# MAIN_DRIVER.net
KiCad netlist of a schematic drawn in Altium Designer
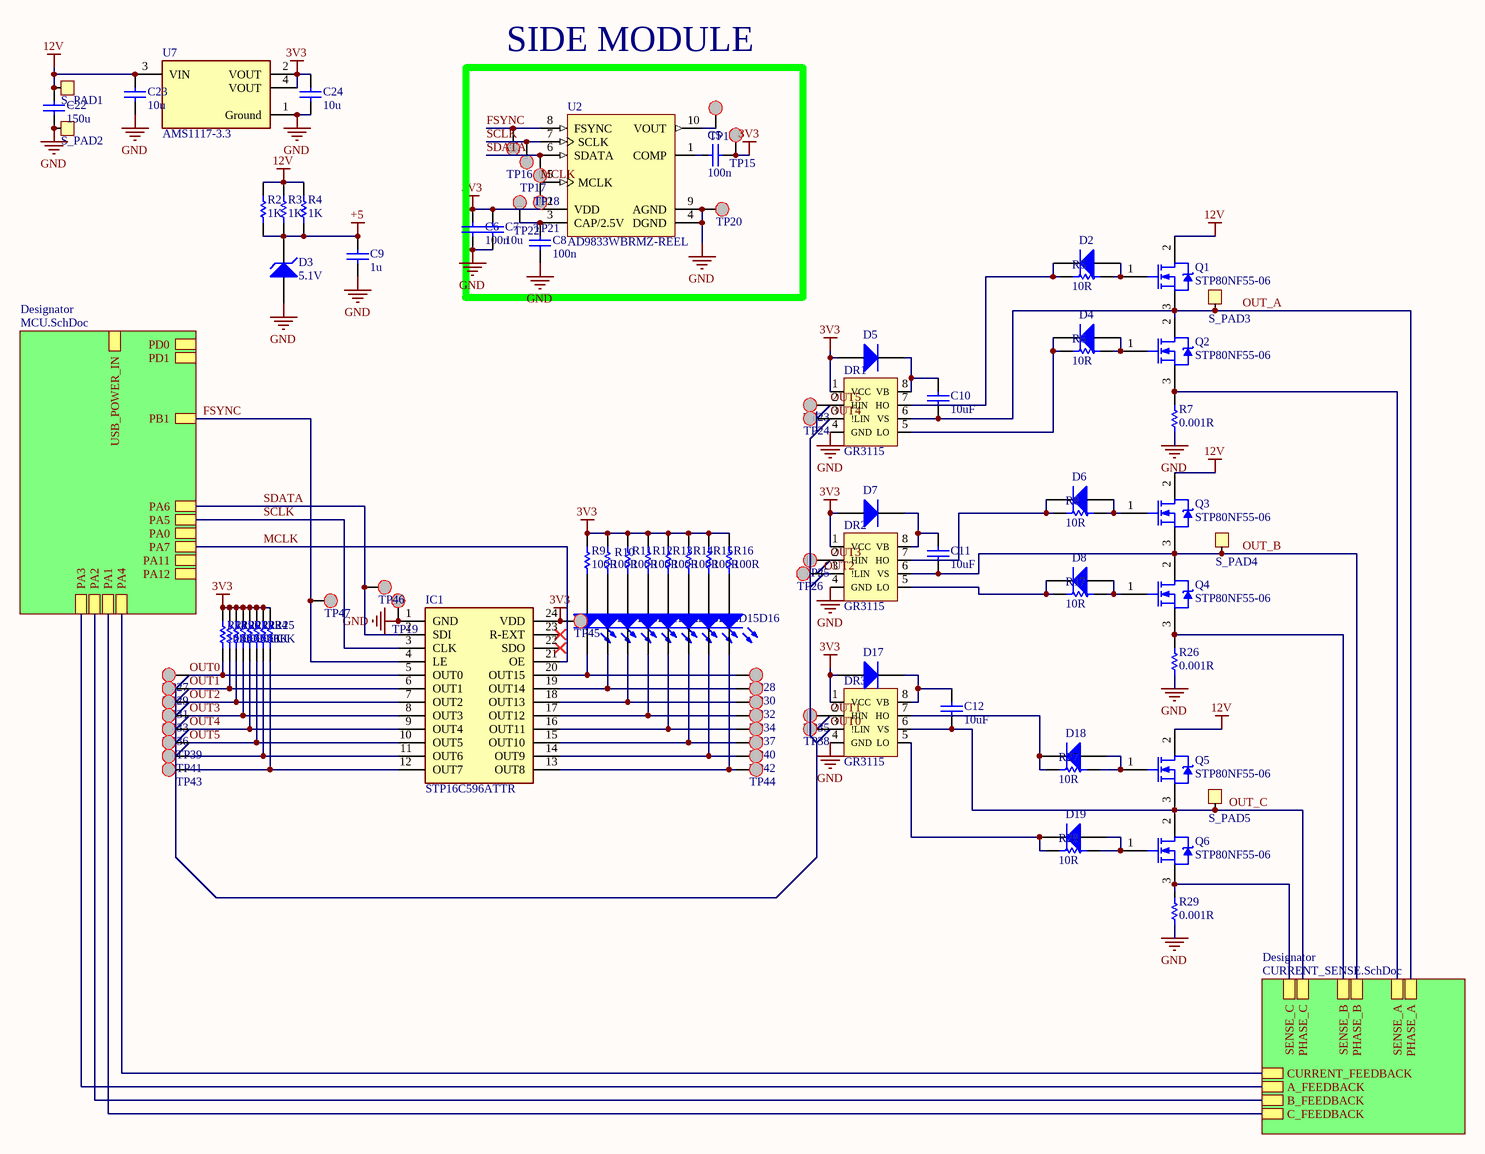
[diagram p0: MAIN_DRIVER.SchDoc]

(export (version "E")
  (design (tool "Eeschema 10.0.6"))
  (components
    (comp (ref "C5")
      (value "100n")
      (footprint "CAP FILM 0603_1608")
      (description "Capacitor")
      (libsource (lib "Simulation Generic Components") (part "Capacitor"))
    )
    (comp (ref "C6")
      (value "100n")
      (footprint "CAP FILM 0603_1608")
      (description "Capacitor")
      (libsource (lib "Simulation Generic Components") (part "Capacitor"))
    )
    (comp (ref "C7")
      (value "10u")
      (footprint "CAP FILM 0603_1608")
      (description "Capacitor")
      (libsource (lib "Simulation Generic Components") (part "Capacitor"))
    )
    (comp (ref "C8")
      (value "100n")
      (footprint "CAP FILM 0603_1608")
      (description "Capacitor")
      (libsource (lib "Simulation Generic Components") (part "Capacitor"))
    )
    (comp (ref "C9")
      (value "1u")
      (footprint "CAP FILM 0603_1608")
      (description "Capacitor")
      (libsource (lib "Simulation Generic Components") (part "Capacitor"))
    )
    (comp (ref "C10")
      (value "10uF")
      (footprint "CAP FILM 0603_1608")
      (description "Capacitor")
      (libsource (lib "Simulation Generic Components") (part "Capacitor"))
    )
    (comp (ref "C11")
      (value "10uF")
      (footprint "CAP FILM 0603_1608")
      (description "Capacitor")
      (libsource (lib "Simulation Generic Components") (part "Capacitor"))
    )
    (comp (ref "C12")
      (value "10uF")
      (footprint "CAP FILM 0603_1608")
      (description "Capacitor")
      (libsource (lib "Simulation Generic Components") (part "Capacitor"))
    )
    (comp (ref "C22")
      (value "150u")
      (footprint "CAPAE7266X80M")
      (description "Capacitor")
      (libsource (lib "Simulation Generic Components") (part "Capacitor"))
    )
    (comp (ref "C23")
      (value "10u")
      (footprint "CAP FILM 0805")
      (description "Capacitor")
      (libsource (lib "Simulation Generic Components") (part "Capacitor"))
    )
    (comp (ref "C24")
      (value "10u")
      (footprint "CAP FILM 0805")
      (description "Capacitor")
      (libsource (lib "Simulation Generic Components") (part "Capacitor"))
    )
    (comp (ref "D2")
      (value "1N4148")
      (footprint "SODFL375X135-2N")
      (description "Diode")
      (libsource (lib "Simulation Generic Components") (part "Diode"))
    )
    (comp (ref "D3")
      (value "Zener Diode")
      (footprint "DIOMELF3514N")
      (fields (field (name "BV") "5.1V"))
      (libsource (lib "Simulation Generic Components") (part "Zener Diode"))
    )
    (comp (ref "D4")
      (value "1N4148")
      (footprint "SODFL375X135-2N")
      (description "Diode")
      (libsource (lib "Simulation Generic Components") (part "Diode"))
    )
    (comp (ref "D5")
      (value "Diode")
      (footprint "SODFL365X110-2N")
      (libsource (lib "Simulation Generic Components") (part "Diode"))
    )
    (comp (ref "D6")
      (value "1N4148")
      (footprint "SODFL375X135-2N")
      (description "Diode")
      (libsource (lib "Simulation Generic Components") (part "Diode"))
    )
    (comp (ref "D7")
      (value "Diode")
      (footprint "SODFL365X110-2N")
      (libsource (lib "Simulation Generic Components") (part "Diode"))
    )
    (comp (ref "D8")
      (value "1N4148")
      (footprint "SODFL375X135-2N")
      (description "Diode")
      (libsource (lib "Simulation Generic Components") (part "Diode"))
    )
    (comp (ref "D9")
      (value "Light-Emitting Diode")
      (footprint "RES 0603_1608")
      (libsource (lib "Simulation Generic Components") (part "LED"))
    )
    (comp (ref "D10")
      (value "Light-Emitting Diode")
      (footprint "RES 0603_1608")
      (libsource (lib "Simulation Generic Components") (part "LED"))
    )
    (comp (ref "D11")
      (value "Light-Emitting Diode")
      (footprint "RES 0603_1608")
      (libsource (lib "Simulation Generic Components") (part "LED"))
    )
    (comp (ref "D12")
      (value "Light-Emitting Diode")
      (footprint "RES 0603_1608")
      (libsource (lib "Simulation Generic Components") (part "LED"))
    )
    (comp (ref "D13")
      (value "Light-Emitting Diode")
      (footprint "RES 0603_1608")
      (libsource (lib "Simulation Generic Components") (part "LED"))
    )
    (comp (ref "D14")
      (value "Light-Emitting Diode")
      (footprint "RES 0603_1608")
      (libsource (lib "Simulation Generic Components") (part "LED"))
    )
    (comp (ref "D15")
      (value "Light-Emitting Diode")
      (footprint "RES 0603_1608")
      (libsource (lib "Simulation Generic Components") (part "LED"))
    )
    (comp (ref "D16")
      (value "Light-Emitting Diode")
      (footprint "RES 0603_1608")
      (libsource (lib "Simulation Generic Components") (part "LED"))
    )
    (comp (ref "D17")
      (value "Diode")
      (footprint "SODFL365X110-2N")
      (libsource (lib "Simulation Generic Components") (part "Diode"))
    )
    (comp (ref "D18")
      (value "1N4148")
      (footprint "SODFL375X135-2N")
      (description "Diode")
      (libsource (lib "Simulation Generic Components") (part "Diode"))
    )
    (comp (ref "D19")
      (value "1N4148")
      (footprint "SODFL375X135-2N")
      (description "Diode")
      (libsource (lib "Simulation Generic Components") (part "Diode"))
    )
    (comp (ref "DR1")
      (value "GR3115")
      (footprint "PCBComponent_1")
      (libsource (lib "GR3115") (part "GR3115"))
    )
    (comp (ref "DR2")
      (value "GR3115")
      (footprint "PCBComponent_1")
      (libsource (lib "GR3115") (part "GR3115"))
    )
    (comp (ref "DR3")
      (value "GR3115")
      (footprint "PCBComponent_1")
      (libsource (lib "GR3115") (part "GR3115"))
    )
    (comp (ref "IC1")
      (value "STP16C596ATTR")
      (footprint "SamacSys:SOP65P638X110-24N")
      (description "Integrated Circuit")
      (libsource (lib "*") (part "STP16C596ATTR"))
    )
    (comp (ref "Q1")
      (value "STP80NF55-06")
      (footprint "STM-TO-220A-3")
      (fields (field (name "MANUFACTURER") "STMicroelectronics"))
      (libsource (lib "Altium Content Vault") (part "NEMOS-GDS-3_B"))
    )
    (comp (ref "Q2")
      (value "STP80NF55-06")
      (footprint "STM-TO-220A-3")
      (fields (field (name "MANUFACTURER") "STMicroelectronics"))
      (libsource (lib "Altium Content Vault") (part "NEMOS-GDS-3_B"))
    )
    (comp (ref "Q3")
      (value "STP80NF55-06")
      (footprint "STM-TO-220A-3")
      (fields (field (name "MANUFACTURER") "STMicroelectronics"))
      (libsource (lib "Altium Content Vault") (part "NEMOS-GDS-3_B"))
    )
    (comp (ref "Q4")
      (value "STP80NF55-06")
      (footprint "STM-TO-220A-3")
      (fields (field (name "MANUFACTURER") "STMicroelectronics"))
      (libsource (lib "Altium Content Vault") (part "NEMOS-GDS-3_B"))
    )
    (comp (ref "Q5")
      (value "STP80NF55-06")
      (footprint "STM-TO-220A-3")
      (fields (field (name "MANUFACTURER") "STMicroelectronics"))
      (libsource (lib "Altium Content Vault") (part "NEMOS-GDS-3_B"))
    )
    (comp (ref "Q6")
      (value "STP80NF55-06")
      (footprint "STM-TO-220A-3")
      (fields (field (name "MANUFACTURER") "STMicroelectronics"))
      (libsource (lib "Altium Content Vault") (part "NEMOS-GDS-3_B"))
    )
    (comp (ref "R2")
      (value "1K")
      (footprint "RES 0603_1608")
      (description "Resistor")
      (libsource (lib "Simulation Generic Components") (part "Resistor"))
    )
    (comp (ref "R3")
      (value "1K")
      (footprint "RES 0603_1608")
      (description "Resistor")
      (libsource (lib "Simulation Generic Components") (part "Resistor"))
    )
    (comp (ref "R4")
      (value "1K")
      (footprint "RES 0603_1608")
      (description "Resistor")
      (libsource (lib "Simulation Generic Components") (part "Resistor"))
    )
    (comp (ref "R5")
      (value "10R")
      (footprint "RES 0603_1608")
      (description "Resistor")
      (libsource (lib "Simulation Generic Components") (part "Resistor"))
    )
    (comp (ref "R6")
      (value "10R")
      (footprint "RES 0603_1608")
      (description "Resistor")
      (libsource (lib "Simulation Generic Components") (part "Resistor"))
    )
    (comp (ref "R7")
      (value "0.001R")
      (footprint "RES 1206_3216")
      (description "Resistor")
      (libsource (lib "Simulation Generic Components") (part "Resistor"))
    )
    (comp (ref "R8")
      (value "10R")
      (footprint "RES 0603_1608")
      (description "Resistor")
      (libsource (lib "Simulation Generic Components") (part "Resistor"))
    )
    (comp (ref "R9")
      (value "100R")
      (footprint "RES 0603_1608")
      (description "Resistor")
      (libsource (lib "Simulation Generic Components") (part "Resistor"))
    )
    (comp (ref "R10")
      (value "100R")
      (footprint "RES 0603_1608")
      (description "Resistor")
      (libsource (lib "Simulation Generic Components") (part "Resistor"))
    )
    (comp (ref "R11")
      (value "100R")
      (footprint "RES 0603_1608")
      (description "Resistor")
      (libsource (lib "Simulation Generic Components") (part "Resistor"))
    )
    (comp (ref "R12")
      (value "100R")
      (footprint "RES 0603_1608")
      (description "Resistor")
      (libsource (lib "Simulation Generic Components") (part "Resistor"))
    )
    (comp (ref "R13")
      (value "100R")
      (footprint "RES 0603_1608")
      (description "Resistor")
      (libsource (lib "Simulation Generic Components") (part "Resistor"))
    )
    (comp (ref "R14")
      (value "100R")
      (footprint "RES 0603_1608")
      (description "Resistor")
      (libsource (lib "Simulation Generic Components") (part "Resistor"))
    )
    (comp (ref "R15")
      (value "100R")
      (footprint "RES 0603_1608")
      (description "Resistor")
      (libsource (lib "Simulation Generic Components") (part "Resistor"))
    )
    (comp (ref "R16")
      (value "100R")
      (footprint "RES 0603_1608")
      (description "Resistor")
      (libsource (lib "Simulation Generic Components") (part "Resistor"))
    )
    (comp (ref "R17")
      (value "10R")
      (footprint "RES 0603_1608")
      (description "Resistor")
      (libsource (lib "Simulation Generic Components") (part "Resistor"))
    )
    (comp (ref "R18")
      (value "10K")
      (footprint "RES 0603_1608")
      (description "Resistor")
      (libsource (lib "Simulation Generic Components") (part "Resistor"))
    )
    (comp (ref "R19")
      (value "10K")
      (footprint "RES 0603_1608")
      (description "Resistor")
      (libsource (lib "Simulation Generic Components") (part "Resistor"))
    )
    (comp (ref "R20")
      (value "10K")
      (footprint "RES 0603_1608")
      (description "Resistor")
      (libsource (lib "Simulation Generic Components") (part "Resistor"))
    )
    (comp (ref "R21")
      (value "10K")
      (footprint "RES 0603_1608")
      (description "Resistor")
      (libsource (lib "Simulation Generic Components") (part "Resistor"))
    )
    (comp (ref "R22")
      (value "10K")
      (footprint "RES 0603_1608")
      (description "Resistor")
      (libsource (lib "Simulation Generic Components") (part "Resistor"))
    )
    (comp (ref "R23")
      (value "10K")
      (footprint "RES 0603_1608")
      (description "Resistor")
      (libsource (lib "Simulation Generic Components") (part "Resistor"))
    )
    (comp (ref "R24")
      (value "10K")
      (footprint "RES 0603_1608")
      (description "Resistor")
      (libsource (lib "Simulation Generic Components") (part "Resistor"))
    )
    (comp (ref "R25")
      (value "10K")
      (footprint "RES 0603_1608")
      (description "Resistor")
      (libsource (lib "Simulation Generic Components") (part "Resistor"))
    )
    (comp (ref "R26")
      (value "0.001R")
      (footprint "RES 1206_3216")
      (description "Resistor")
      (libsource (lib "Simulation Generic Components") (part "Resistor"))
    )
    (comp (ref "R27")
      (value "10R")
      (footprint "RES 0603_1608")
      (description "Resistor")
      (libsource (lib "Simulation Generic Components") (part "Resistor"))
    )
    (comp (ref "R28")
      (value "10R")
      (footprint "RES 0603_1608")
      (description "Resistor")
      (libsource (lib "Simulation Generic Components") (part "Resistor"))
    )
    (comp (ref "R29")
      (value "0.001R")
      (footprint "RES 1206_3216")
      (description "Resistor")
      (libsource (lib "Simulation Generic Components") (part "Resistor"))
    )
    (comp (ref "S_PAD1")
      (value "SOLDER_PAD")
      (footprint "POWER_PAD")
      (libsource (lib "solderpad") (part "SOLDER_PAD"))
    )
    (comp (ref "S_PAD2")
      (value "SOLDER_PAD")
      (footprint "POWER_PAD")
      (libsource (lib "solderpad") (part "SOLDER_PAD"))
    )
    (comp (ref "S_PAD3")
      (value "SOLDER_PAD")
      (footprint "POWER_PAD")
      (libsource (lib "") (part "SOLDER_PAD_1"))
    )
    (comp (ref "S_PAD4")
      (value "SOLDER_PAD")
      (footprint "POWER_PAD")
      (libsource (lib "") (part "SOLDER_PAD_1"))
    )
    (comp (ref "S_PAD5")
      (value "SOLDER_PAD")
      (footprint "POWER_PAD")
      (libsource (lib "") (part "SOLDER_PAD_1"))
    )
    (comp (ref "TP14") (value "~") (footprint "ROUND_SMALL") (libsource (lib "solderpad") (part "TEST_PAD")))
    (comp (ref "TP15") (value "~") (footprint "ROUND_SMALL") (libsource (lib "solderpad") (part "TEST_PAD")))
    (comp (ref "TP16") (value "~") (footprint "ROUND_SMALL") (libsource (lib "solderpad") (part "TEST_PAD")))
    (comp (ref "TP17") (value "~") (footprint "ROUND_SMALL") (libsource (lib "solderpad") (part "TEST_PAD")))
    (comp (ref "TP18") (value "~") (footprint "ROUND_SMALL") (libsource (lib "solderpad") (part "TEST_PAD")))
    (comp (ref "TP19") (value "~") (footprint "ROUND_SMALL") (libsource (lib "solderpad") (part "TEST_PAD")))
    (comp (ref "TP20") (value "~") (footprint "ROUND_SMALL") (libsource (lib "solderpad") (part "TEST_PAD")))
    (comp (ref "TP21") (value "~") (footprint "ROUND_SMALL") (libsource (lib "solderpad") (part "TEST_PAD")))
    (comp (ref "TP22") (value "~") (footprint "ROUND_SMALL") (libsource (lib "solderpad") (part "TEST_PAD")))
    (comp (ref "TP23") (value "~") (footprint "ROUND_SMALL") (libsource (lib "solderpad") (part "TEST_PAD")))
    (comp (ref "TP24") (value "~") (footprint "ROUND_SMALL") (libsource (lib "solderpad") (part "TEST_PAD")))
    (comp (ref "TP25") (value "~") (footprint "ROUND_SMALL") (libsource (lib "solderpad") (part "TEST_PAD")))
    (comp (ref "TP26") (value "~") (footprint "ROUND_SMALL") (libsource (lib "solderpad") (part "TEST_PAD")))
    (comp (ref "TP27") (value "~") (footprint "ROUND_SMALL") (libsource (lib "solderpad") (part "TEST_PAD")))
    (comp (ref "TP28") (value "~") (footprint "ROUND_SMALL") (libsource (lib "solderpad") (part "TEST_PAD")))
    (comp (ref "TP29") (value "~") (footprint "ROUND_SMALL") (libsource (lib "solderpad") (part "TEST_PAD")))
    (comp (ref "TP30") (value "~") (footprint "ROUND_SMALL") (libsource (lib "solderpad") (part "TEST_PAD")))
    (comp (ref "TP31") (value "~") (footprint "ROUND_SMALL") (libsource (lib "solderpad") (part "TEST_PAD")))
    (comp (ref "TP32") (value "~") (footprint "ROUND_SMALL") (libsource (lib "solderpad") (part "TEST_PAD")))
    (comp (ref "TP33") (value "~") (footprint "ROUND_SMALL") (libsource (lib "solderpad") (part "TEST_PAD")))
    (comp (ref "TP34") (value "~") (footprint "ROUND_SMALL") (libsource (lib "solderpad") (part "TEST_PAD")))
    (comp (ref "TP35") (value "~") (footprint "ROUND_SMALL") (libsource (lib "solderpad") (part "TEST_PAD")))
    (comp (ref "TP36") (value "~") (footprint "ROUND_SMALL") (libsource (lib "solderpad") (part "TEST_PAD")))
    (comp (ref "TP37") (value "~") (footprint "ROUND_SMALL") (libsource (lib "solderpad") (part "TEST_PAD")))
    (comp (ref "TP38") (value "~") (footprint "ROUND_SMALL") (libsource (lib "solderpad") (part "TEST_PAD")))
    (comp (ref "TP39") (value "~") (footprint "ROUND_SMALL") (libsource (lib "solderpad") (part "TEST_PAD")))
    (comp (ref "TP40") (value "~") (footprint "ROUND_SMALL") (libsource (lib "solderpad") (part "TEST_PAD")))
    (comp (ref "TP41") (value "~") (footprint "ROUND_SMALL") (libsource (lib "solderpad") (part "TEST_PAD")))
    (comp (ref "TP42") (value "~") (footprint "ROUND_SMALL") (libsource (lib "solderpad") (part "TEST_PAD")))
    (comp (ref "TP43") (value "~") (footprint "ROUND_SMALL") (libsource (lib "solderpad") (part "TEST_PAD")))
    (comp (ref "TP44") (value "~") (footprint "ROUND_SMALL") (libsource (lib "solderpad") (part "TEST_PAD")))
    (comp (ref "TP45") (value "~") (footprint "ROUND_SMALL") (libsource (lib "solderpad") (part "TEST_PAD")))
    (comp (ref "TP46") (value "~") (footprint "ROUND_SMALL") (libsource (lib "solderpad") (part "TEST_PAD")))
    (comp (ref "TP47") (value "~") (footprint "ROUND_SMALL") (libsource (lib "solderpad") (part "TEST_PAD")))
    (comp (ref "U2")
      (value "AD9833WBRMZ-REEL")
      (footprint "ADI-RM-10_M")
      (libsource (lib "Altium Content Vault") (part "ADI-AD9833-RM-10"))
    )
    (comp (ref "U7")
      (value "AMS1117-3.3")
      (footprint "FP-AMS1117-IPC_C")
      (description "LDO Voltage Regulators 1A, 3.3V")
      (fields
        (field (name "OCTOPART") "https://octopart.com/ams1117-3.3-advanced+monolithic+systems-25899300")
        (field (name "MANUFACTURER") "Advanced Monolithic Systems")
      )
      (libsource (lib "Altium Content Vault") (part "8bdbb5f8e77002000e30dd2845d0354"))
    )
  )
  (nets
    (net (code "1") (name "+5") (class "Default")
      (node (ref "C9") (pin "2") (pinfunction "2_2") (pintype "passive"))
      (node (ref "D3") (pin "2") (pinfunction "K_2") (pintype "passive"))
      (node (ref "R2") (pin "1") (pinfunction "1_1") (pintype "passive"))
      (node (ref "R3") (pin "1") (pinfunction "1_1") (pintype "passive"))
      (node (ref "R4") (pin "1") (pinfunction "1_1") (pintype "passive"))
    )
    (net (code "6") (name "/FSYNC") (class "Default")
      (node (ref "IC1") (pin "4") (pinfunction "LE_4") (pintype "passive"))
      (node (ref "TP16") (pin "1") (pinfunction "Test_Point_1") (pintype "passive"))
      (node (ref "TP47") (pin "1") (pinfunction "Test_Point_1") (pintype "passive"))
      (node (ref "U2") (pin "8") (pinfunction "FSYNC_8") (pintype "input"))
    )
    (net (code "7") (name "/MCLK") (class "Default")
      (node (ref "IC1") (pin "21") (pinfunction "OE_21") (pintype "passive"))
      (node (ref "TP21") (pin "1") (pinfunction "Test_Point_1") (pintype "passive"))
      (node (ref "U2") (pin "5") (pinfunction "MCLK_5") (pintype "input"))
    )
    (net (code "8") (name "/OUT0") (class "Default")
      (node (ref "DR3") (pin "3") (pinfunction "!LIN_3") (pintype "passive"))
      (node (ref "IC1") (pin "5") (pinfunction "OUT0_5") (pintype "passive"))
      (node (ref "R18") (pin "1") (pinfunction "1_1") (pintype "passive"))
      (node (ref "TP27") (pin "1") (pinfunction "Test_Point_1") (pintype "passive"))
      (node (ref "TP38") (pin "1") (pinfunction "Test_Point_1") (pintype "passive"))
    )
    (net (code "9") (name "/OUT1") (class "Default")
      (node (ref "DR3") (pin "2") (pinfunction "HIN_2") (pintype "passive"))
      (node (ref "IC1") (pin "6") (pinfunction "OUT1_6") (pintype "passive"))
      (node (ref "R19") (pin "1") (pinfunction "1_1") (pintype "passive"))
      (node (ref "TP29") (pin "1") (pinfunction "Test_Point_1") (pintype "passive"))
      (node (ref "TP35") (pin "1") (pinfunction "Test_Point_1") (pintype "passive"))
    )
    (net (code "10") (name "/OUT2") (class "Default")
      (node (ref "DR2") (pin "3") (pinfunction "!LIN_3") (pintype "passive"))
      (node (ref "IC1") (pin "7") (pinfunction "OUT2_7") (pintype "passive"))
      (node (ref "R20") (pin "1") (pinfunction "1_1") (pintype "passive"))
      (node (ref "TP26") (pin "1") (pinfunction "Test_Point_1") (pintype "passive"))
      (node (ref "TP31") (pin "1") (pinfunction "Test_Point_1") (pintype "passive"))
    )
    (net (code "11") (name "/OUT3") (class "Default")
      (node (ref "DR2") (pin "2") (pinfunction "HIN_2") (pintype "passive"))
      (node (ref "IC1") (pin "8") (pinfunction "OUT3_8") (pintype "passive"))
      (node (ref "R21") (pin "1") (pinfunction "1_1") (pintype "passive"))
      (node (ref "TP25") (pin "1") (pinfunction "Test_Point_1") (pintype "passive"))
      (node (ref "TP33") (pin "1") (pinfunction "Test_Point_1") (pintype "passive"))
    )
    (net (code "12") (name "/OUT4") (class "Default")
      (node (ref "DR1") (pin "3") (pinfunction "!LIN_3") (pintype "passive"))
      (node (ref "IC1") (pin "9") (pinfunction "OUT4_9") (pintype "passive"))
      (node (ref "R22") (pin "1") (pinfunction "1_1") (pintype "passive"))
      (node (ref "TP24") (pin "1") (pinfunction "Test_Point_1") (pintype "passive"))
      (node (ref "TP36") (pin "1") (pinfunction "Test_Point_1") (pintype "passive"))
    )
    (net (code "13") (name "/OUT5") (class "Default")
      (node (ref "DR1") (pin "2") (pinfunction "HIN_2") (pintype "passive"))
      (node (ref "IC1") (pin "10") (pinfunction "OUT5_10") (pintype "passive"))
      (node (ref "R23") (pin "1") (pinfunction "1_1") (pintype "passive"))
      (node (ref "TP23") (pin "1") (pinfunction "Test_Point_1") (pintype "passive"))
      (node (ref "TP39") (pin "1") (pinfunction "Test_Point_1") (pintype "passive"))
    )
    (net (code "14") (name "/OUT_A") (class "Default")
      (node (ref "C10") (pin "1") (pinfunction "1_1") (pintype "passive"))
      (node (ref "DR1") (pin "6") (pinfunction "VS_6") (pintype "passive"))
      (node (ref "Q1") (pin "3") (pinfunction "S_3") (pintype "passive"))
      (node (ref "Q2") (pin "2") (pinfunction "D_2") (pintype "passive"))
      (node (ref "S_PAD3") (pin "1") (pinfunction "0_1") (pintype "passive"))
    )
    (net (code "15") (name "/OUT_B") (class "Default")
      (node (ref "C11") (pin "2") (pinfunction "2_2") (pintype "passive"))
      (node (ref "DR2") (pin "6") (pinfunction "VS_6") (pintype "passive"))
      (node (ref "Q3") (pin "3") (pinfunction "S_3") (pintype "passive"))
      (node (ref "Q4") (pin "2") (pinfunction "D_2") (pintype "passive"))
      (node (ref "S_PAD4") (pin "1") (pinfunction "0_1") (pintype "passive"))
    )
    (net (code "16") (name "/OUT_C") (class "Default")
      (node (ref "C12") (pin "1") (pinfunction "1_1") (pintype "passive"))
      (node (ref "DR3") (pin "6") (pinfunction "VS_6") (pintype "passive"))
      (node (ref "Q5") (pin "3") (pinfunction "S_3") (pintype "passive"))
      (node (ref "Q6") (pin "2") (pinfunction "D_2") (pintype "passive"))
      (node (ref "S_PAD5") (pin "1") (pinfunction "0_1") (pintype "passive"))
    )
    (net (code "22") (name "/SCLK") (class "Default")
      (node (ref "IC1") (pin "3") (pinfunction "CLK_3") (pintype "passive"))
      (node (ref "TP17") (pin "1") (pinfunction "Test_Point_1") (pintype "passive"))
      (node (ref "U2") (pin "7") (pinfunction "SCLK_7") (pintype "input"))
    )
    (net (code "23") (name "/SDATA") (class "Default")
      (node (ref "IC1") (pin "2") (pinfunction "SDI_2") (pintype "passive"))
      (node (ref "TP18") (pin "1") (pinfunction "Test_Point_1") (pintype "passive"))
      (node (ref "TP46") (pin "1") (pinfunction "Test_Point_1") (pintype "passive"))
      (node (ref "U2") (pin "6") (pinfunction "SDATA_6") (pintype "input"))
    )
    (net (code "24") (name "/SENSE_A") (class "Default")
      (node (ref "Q2") (pin "3") (pinfunction "S_3") (pintype "passive"))
      (node (ref "R7") (pin "2") (pinfunction "2_2") (pintype "passive"))
    )
    (net (code "25") (name "/SENSE_B") (class "Default")
      (node (ref "Q4") (pin "3") (pinfunction "S_3") (pintype "passive"))
      (node (ref "R26") (pin "2") (pinfunction "2_2") (pintype "passive"))
    )
    (net (code "26") (name "/SENSE_C") (class "Default")
      (node (ref "Q6") (pin "3") (pinfunction "S_3") (pintype "passive"))
      (node (ref "R29") (pin "2") (pinfunction "2_2") (pintype "passive"))
    )
    (net (code "28") (name "3V3") (class "Default")
      (node (ref "C24") (pin "2") (pinfunction "2_2") (pintype "passive"))
      (node (ref "C5") (pin "2") (pinfunction "2_2") (pintype "passive"))
      (node (ref "C6") (pin "2") (pinfunction "2_2") (pintype "passive"))
      (node (ref "C7") (pin "1") (pinfunction "1_1") (pintype "passive"))
      (node (ref "D17") (pin "1") (pinfunction "A_1") (pintype "passive"))
      (node (ref "D5") (pin "1") (pinfunction "A_1") (pintype "passive"))
      (node (ref "D7") (pin "1") (pinfunction "A_1") (pintype "passive"))
      (node (ref "DR1") (pin "1") (pinfunction "VCC_1") (pintype "passive"))
      (node (ref "DR2") (pin "1") (pinfunction "VCC_1") (pintype "passive"))
      (node (ref "DR3") (pin "1") (pinfunction "VCC_1") (pintype "passive"))
      (node (ref "IC1") (pin "24") (pinfunction "VDD_24") (pintype "passive"))
      (node (ref "R10") (pin "2") (pinfunction "2_2") (pintype "passive"))
      (node (ref "R11") (pin "2") (pinfunction "2_2") (pintype "passive"))
      (node (ref "R12") (pin "2") (pinfunction "2_2") (pintype "passive"))
      (node (ref "R13") (pin "2") (pinfunction "2_2") (pintype "passive"))
      (node (ref "R14") (pin "2") (pinfunction "2_2") (pintype "passive"))
      (node (ref "R15") (pin "2") (pinfunction "2_2") (pintype "passive"))
      (node (ref "R16") (pin "2") (pinfunction "2_2") (pintype "passive"))
      (node (ref "R18") (pin "2") (pinfunction "2_2") (pintype "passive"))
      (node (ref "R19") (pin "2") (pinfunction "2_2") (pintype "passive"))
      (node (ref "R20") (pin "2") (pinfunction "2_2") (pintype "passive"))
      (node (ref "R21") (pin "2") (pinfunction "2_2") (pintype "passive"))
      (node (ref "R22") (pin "2") (pinfunction "2_2") (pintype "passive"))
      (node (ref "R23") (pin "2") (pinfunction "2_2") (pintype "passive"))
      (node (ref "R24") (pin "2") (pinfunction "2_2") (pintype "passive"))
      (node (ref "R25") (pin "2") (pinfunction "2_2") (pintype "passive"))
      (node (ref "R9") (pin "2") (pinfunction "2_2") (pintype "passive"))
      (node (ref "TP15") (pin "1") (pinfunction "Test_Point_1") (pintype "passive"))
      (node (ref "TP45") (pin "1") (pinfunction "Test_Point_1") (pintype "passive"))
      (node (ref "U2") (pin "2") (pinfunction "VDD_2") (pintype "power_in"))
      (node (ref "U7") (pin "2") (pinfunction "VOUT_2") (pintype "passive"))
      (node (ref "U7") (pin "4") (pinfunction "VOUT_4") (pintype "passive"))
    )
    (net (code "29") (name "12V") (class "Default")
      (node (ref "C22") (pin "2") (pinfunction "2_2") (pintype "passive"))
      (node (ref "C23") (pin "2") (pinfunction "2_2") (pintype "passive"))
      (node (ref "Q1") (pin "2") (pinfunction "D_2") (pintype "passive"))
      (node (ref "Q3") (pin "2") (pinfunction "D_2") (pintype "passive"))
      (node (ref "Q5") (pin "2") (pinfunction "D_2") (pintype "passive"))
      (node (ref "R2") (pin "2") (pinfunction "2_2") (pintype "passive"))
      (node (ref "R3") (pin "2") (pinfunction "2_2") (pintype "passive"))
      (node (ref "R4") (pin "2") (pinfunction "2_2") (pintype "passive"))
      (node (ref "S_PAD1") (pin "1") (pinfunction "0_1") (pintype "passive"))
      (node (ref "U7") (pin "3") (pinfunction "VIN_3") (pintype "power_in"))
    )
    (net (code "30") (name "GND") (class "Default")
      (node (ref "C22") (pin "1") (pinfunction "1_1") (pintype "passive"))
      (node (ref "C23") (pin "1") (pinfunction "1_1") (pintype "passive"))
      (node (ref "C24") (pin "1") (pinfunction "1_1") (pintype "passive"))
      (node (ref "C6") (pin "1") (pinfunction "1_1") (pintype "passive"))
      (node (ref "C7") (pin "2") (pinfunction "2_2") (pintype "passive"))
      (node (ref "C8") (pin "1") (pinfunction "1_1") (pintype "passive"))
      (node (ref "C9") (pin "1") (pinfunction "1_1") (pintype "passive"))
      (node (ref "D3") (pin "1") (pinfunction "A_1") (pintype "passive"))
      (node (ref "DR1") (pin "4") (pinfunction "GND_4") (pintype "passive"))
      (node (ref "DR2") (pin "4") (pinfunction "GND_4") (pintype "passive"))
      (node (ref "DR3") (pin "4") (pinfunction "GND_4") (pintype "passive"))
      (node (ref "IC1") (pin "1") (pinfunction "GND_1") (pintype "passive"))
      (node (ref "R26") (pin "1") (pinfunction "1_1") (pintype "passive"))
      (node (ref "R29") (pin "1") (pinfunction "1_1") (pintype "passive"))
      (node (ref "R7") (pin "1") (pinfunction "1_1") (pintype "passive"))
      (node (ref "S_PAD2") (pin "1") (pinfunction "0_1") (pintype "passive"))
      (node (ref "TP19") (pin "1") (pinfunction "Test_Point_1") (pintype "passive"))
      (node (ref "TP20") (pin "1") (pinfunction "Test_Point_1") (pintype "passive"))
      (node (ref "U2") (pin "4") (pinfunction "DGND_4") (pintype "power_in"))
      (node (ref "U2") (pin "9") (pinfunction "AGND_9") (pintype "power_in"))
      (node (ref "U7") (pin "1") (pinfunction "Ground_1") (pintype "power_in"))
    )
    (net (code "31") (name "Net-(D2-A)") (class "Default")
      (node (ref "D2") (pin "1") (pinfunction "A_1") (pintype "passive"))
      (node (ref "Q1") (pin "1") (pinfunction "G_1") (pintype "passive"))
      (node (ref "R5") (pin "2") (pinfunction "2_2") (pintype "passive"))
    )
    (net (code "32") (name "Net-(D2-K)") (class "Default")
      (node (ref "D2") (pin "2") (pinfunction "K_2") (pintype "passive"))
      (node (ref "DR1") (pin "7") (pinfunction "HO_7") (pintype "passive"))
      (node (ref "R5") (pin "1") (pinfunction "1_1") (pintype "passive"))
    )
    (net (code "33") (name "Net-(D4-A)") (class "Default")
      (node (ref "D4") (pin "1") (pinfunction "A_1") (pintype "passive"))
      (node (ref "Q2") (pin "1") (pinfunction "G_1") (pintype "passive"))
      (node (ref "R6") (pin "2") (pinfunction "2_2") (pintype "passive"))
    )
    (net (code "34") (name "Net-(D4-K)") (class "Default")
      (node (ref "D4") (pin "2") (pinfunction "K_2") (pintype "passive"))
      (node (ref "DR1") (pin "5") (pinfunction "LO_5") (pintype "passive"))
      (node (ref "R6") (pin "1") (pinfunction "1_1") (pintype "passive"))
    )
    (net (code "35") (name "Net-(D5-K)") (class "Default")
      (node (ref "C10") (pin "2") (pinfunction "2_2") (pintype "passive"))
      (node (ref "D5") (pin "2") (pinfunction "K_2") (pintype "passive"))
      (node (ref "DR1") (pin "8") (pinfunction "VB_8") (pintype "passive"))
    )
    (net (code "36") (name "Net-(D6-A)") (class "Default")
      (node (ref "D6") (pin "1") (pinfunction "A_1") (pintype "passive"))
      (node (ref "Q3") (pin "1") (pinfunction "G_1") (pintype "passive"))
      (node (ref "R8") (pin "2") (pinfunction "2_2") (pintype "passive"))
    )
    (net (code "37") (name "Net-(D6-K)") (class "Default")
      (node (ref "D6") (pin "2") (pinfunction "K_2") (pintype "passive"))
      (node (ref "DR2") (pin "7") (pinfunction "HO_7") (pintype "passive"))
      (node (ref "R8") (pin "1") (pinfunction "1_1") (pintype "passive"))
    )
    (net (code "38") (name "Net-(D7-K)") (class "Default")
      (node (ref "C11") (pin "1") (pinfunction "1_1") (pintype "passive"))
      (node (ref "D7") (pin "2") (pinfunction "K_2") (pintype "passive"))
      (node (ref "DR2") (pin "8") (pinfunction "VB_8") (pintype "passive"))
    )
    (net (code "39") (name "Net-(D8-A)") (class "Default")
      (node (ref "D8") (pin "1") (pinfunction "A_1") (pintype "passive"))
      (node (ref "Q4") (pin "1") (pinfunction "G_1") (pintype "passive"))
      (node (ref "R17") (pin "2") (pinfunction "2_2") (pintype "passive"))
    )
    (net (code "40") (name "Net-(D8-K)") (class "Default")
      (node (ref "D8") (pin "2") (pinfunction "K_2") (pintype "passive"))
      (node (ref "DR2") (pin "5") (pinfunction "LO_5") (pintype "passive"))
      (node (ref "R17") (pin "1") (pinfunction "1_1") (pintype "passive"))
    )
    (net (code "41") (name "Net-(D9-A)") (class "Default")
      (node (ref "D9") (pin "1") (pinfunction "A_1") (pintype "passive"))
      (node (ref "R9") (pin "1") (pinfunction "1_1") (pintype "passive"))
    )
    (net (code "42") (name "Net-(D9-K)") (class "Default")
      (node (ref "D9") (pin "2") (pinfunction "K_2") (pintype "passive"))
      (node (ref "IC1") (pin "20") (pinfunction "OUT15_20") (pintype "passive"))
      (node (ref "TP28") (pin "1") (pinfunction "Test_Point_1") (pintype "passive"))
    )
    (net (code "43") (name "Net-(D10-A)") (class "Default")
      (node (ref "D10") (pin "1") (pinfunction "A_1") (pintype "passive"))
      (node (ref "R10") (pin "1") (pinfunction "1_1") (pintype "passive"))
    )
    (net (code "44") (name "Net-(D10-K)") (class "Default")
      (node (ref "D10") (pin "2") (pinfunction "K_2") (pintype "passive"))
      (node (ref "IC1") (pin "19") (pinfunction "OUT14_19") (pintype "passive"))
      (node (ref "TP30") (pin "1") (pinfunction "Test_Point_1") (pintype "passive"))
    )
    (net (code "45") (name "Net-(D11-A)") (class "Default")
      (node (ref "D11") (pin "1") (pinfunction "A_1") (pintype "passive"))
      (node (ref "R11") (pin "1") (pinfunction "1_1") (pintype "passive"))
    )
    (net (code "46") (name "Net-(D11-K)") (class "Default")
      (node (ref "D11") (pin "2") (pinfunction "K_2") (pintype "passive"))
      (node (ref "IC1") (pin "18") (pinfunction "OUT13_18") (pintype "passive"))
      (node (ref "TP32") (pin "1") (pinfunction "Test_Point_1") (pintype "passive"))
    )
    (net (code "47") (name "Net-(D12-A)") (class "Default")
      (node (ref "D12") (pin "1") (pinfunction "A_1") (pintype "passive"))
      (node (ref "R12") (pin "1") (pinfunction "1_1") (pintype "passive"))
    )
    (net (code "48") (name "Net-(D12-K)") (class "Default")
      (node (ref "D12") (pin "2") (pinfunction "K_2") (pintype "passive"))
      (node (ref "IC1") (pin "17") (pinfunction "OUT12_17") (pintype "passive"))
      (node (ref "TP34") (pin "1") (pinfunction "Test_Point_1") (pintype "passive"))
    )
    (net (code "49") (name "Net-(D13-A)") (class "Default")
      (node (ref "D13") (pin "1") (pinfunction "A_1") (pintype "passive"))
      (node (ref "R13") (pin "1") (pinfunction "1_1") (pintype "passive"))
    )
    (net (code "50") (name "Net-(D13-K)") (class "Default")
      (node (ref "D13") (pin "2") (pinfunction "K_2") (pintype "passive"))
      (node (ref "IC1") (pin "16") (pinfunction "OUT11_16") (pintype "passive"))
      (node (ref "TP37") (pin "1") (pinfunction "Test_Point_1") (pintype "passive"))
    )
    (net (code "51") (name "Net-(D14-A)") (class "Default")
      (node (ref "D14") (pin "1") (pinfunction "A_1") (pintype "passive"))
      (node (ref "R14") (pin "1") (pinfunction "1_1") (pintype "passive"))
    )
    (net (code "52") (name "Net-(D14-K)") (class "Default")
      (node (ref "D14") (pin "2") (pinfunction "K_2") (pintype "passive"))
      (node (ref "IC1") (pin "15") (pinfunction "OUT10_15") (pintype "passive"))
      (node (ref "TP40") (pin "1") (pinfunction "Test_Point_1") (pintype "passive"))
    )
    (net (code "53") (name "Net-(D15-A)") (class "Default")
      (node (ref "D15") (pin "1") (pinfunction "A_1") (pintype "passive"))
      (node (ref "R15") (pin "1") (pinfunction "1_1") (pintype "passive"))
    )
    (net (code "54") (name "Net-(D15-K)") (class "Default")
      (node (ref "D15") (pin "2") (pinfunction "K_2") (pintype "passive"))
      (node (ref "IC1") (pin "14") (pinfunction "OUT9_14") (pintype "passive"))
      (node (ref "TP42") (pin "1") (pinfunction "Test_Point_1") (pintype "passive"))
    )
    (net (code "55") (name "Net-(D16-A)") (class "Default")
      (node (ref "D16") (pin "1") (pinfunction "A_1") (pintype "passive"))
      (node (ref "R16") (pin "1") (pinfunction "1_1") (pintype "passive"))
    )
    (net (code "56") (name "Net-(D16-K)") (class "Default")
      (node (ref "D16") (pin "2") (pinfunction "K_2") (pintype "passive"))
      (node (ref "IC1") (pin "13") (pinfunction "OUT8_13") (pintype "passive"))
      (node (ref "TP44") (pin "1") (pinfunction "Test_Point_1") (pintype "passive"))
    )
    (net (code "57") (name "Net-(D17-K)") (class "Default")
      (node (ref "C12") (pin "2") (pinfunction "2_2") (pintype "passive"))
      (node (ref "D17") (pin "2") (pinfunction "K_2") (pintype "passive"))
      (node (ref "DR3") (pin "8") (pinfunction "VB_8") (pintype "passive"))
    )
    (net (code "58") (name "Net-(D18-A)") (class "Default")
      (node (ref "D18") (pin "1") (pinfunction "A_1") (pintype "passive"))
      (node (ref "Q5") (pin "1") (pinfunction "G_1") (pintype "passive"))
      (node (ref "R27") (pin "2") (pinfunction "2_2") (pintype "passive"))
    )
    (net (code "59") (name "Net-(D18-K)") (class "Default")
      (node (ref "D18") (pin "2") (pinfunction "K_2") (pintype "passive"))
      (node (ref "DR3") (pin "7") (pinfunction "HO_7") (pintype "passive"))
      (node (ref "R27") (pin "1") (pinfunction "1_1") (pintype "passive"))
    )
    (net (code "60") (name "Net-(D19-A)") (class "Default")
      (node (ref "D19") (pin "1") (pinfunction "A_1") (pintype "passive"))
      (node (ref "Q6") (pin "1") (pinfunction "G_1") (pintype "passive"))
      (node (ref "R28") (pin "2") (pinfunction "2_2") (pintype "passive"))
    )
    (net (code "61") (name "Net-(D19-K)") (class "Default")
      (node (ref "D19") (pin "2") (pinfunction "K_2") (pintype "passive"))
      (node (ref "DR3") (pin "5") (pinfunction "LO_5") (pintype "passive"))
      (node (ref "R28") (pin "1") (pinfunction "1_1") (pintype "passive"))
    )
    (net (code "62") (name "Net-(IC1-OUT6)") (class "Default")
      (node (ref "IC1") (pin "11") (pinfunction "OUT6_11") (pintype "passive"))
      (node (ref "R24") (pin "1") (pinfunction "1_1") (pintype "passive"))
      (node (ref "TP41") (pin "1") (pinfunction "Test_Point_1") (pintype "passive"))
    )
    (net (code "63") (name "Net-(IC1-OUT7)") (class "Default")
      (node (ref "IC1") (pin "12") (pinfunction "OUT7_12") (pintype "passive"))
      (node (ref "R25") (pin "1") (pinfunction "1_1") (pintype "passive"))
      (node (ref "TP43") (pin "1") (pinfunction "Test_Point_1") (pintype "passive"))
    )
    (net (code "64") (name "Net-(TP14-Test_Point)") (class "Default")
      (node (ref "TP14") (pin "1") (pinfunction "Test_Point_1") (pintype "passive"))
      (node (ref "U2") (pin "10") (pinfunction "VOUT_10") (pintype "output"))
    )
    (net (code "65") (name "Net-(TP22-Test_Point)") (class "Default")
      (node (ref "C8") (pin "2") (pinfunction "2_2") (pintype "passive"))
      (node (ref "TP22") (pin "1") (pinfunction "Test_Point_1") (pintype "passive"))
      (node (ref "U2") (pin "3") (pinfunction "CAP/2.5V_3") (pintype "power_in"))
    )
    (net (code "66") (name "Net-(U2-COMP)") (class "Default")
      (node (ref "C5") (pin "1") (pinfunction "1_1") (pintype "passive"))
      (node (ref "U2") (pin "1") (pinfunction "COMP_1") (pintype "passive"))
    )
    (net (code "67") (name "unconnected-(IC1-R-EXT-Pad23)") (class "Default")
      (node (ref "IC1") (pin "23") (pinfunction "R-EXT_23") (pintype "passive+no_connect"))
    )
    (net (code "68") (name "unconnected-(IC1-SDO-Pad22)") (class "Default")
      (node (ref "IC1") (pin "22") (pinfunction "SDO_22") (pintype "passive+no_connect"))
    )
  )
)
